# Distance_sensors.net
KiCad netlist of a schematic drawn in EAGLE
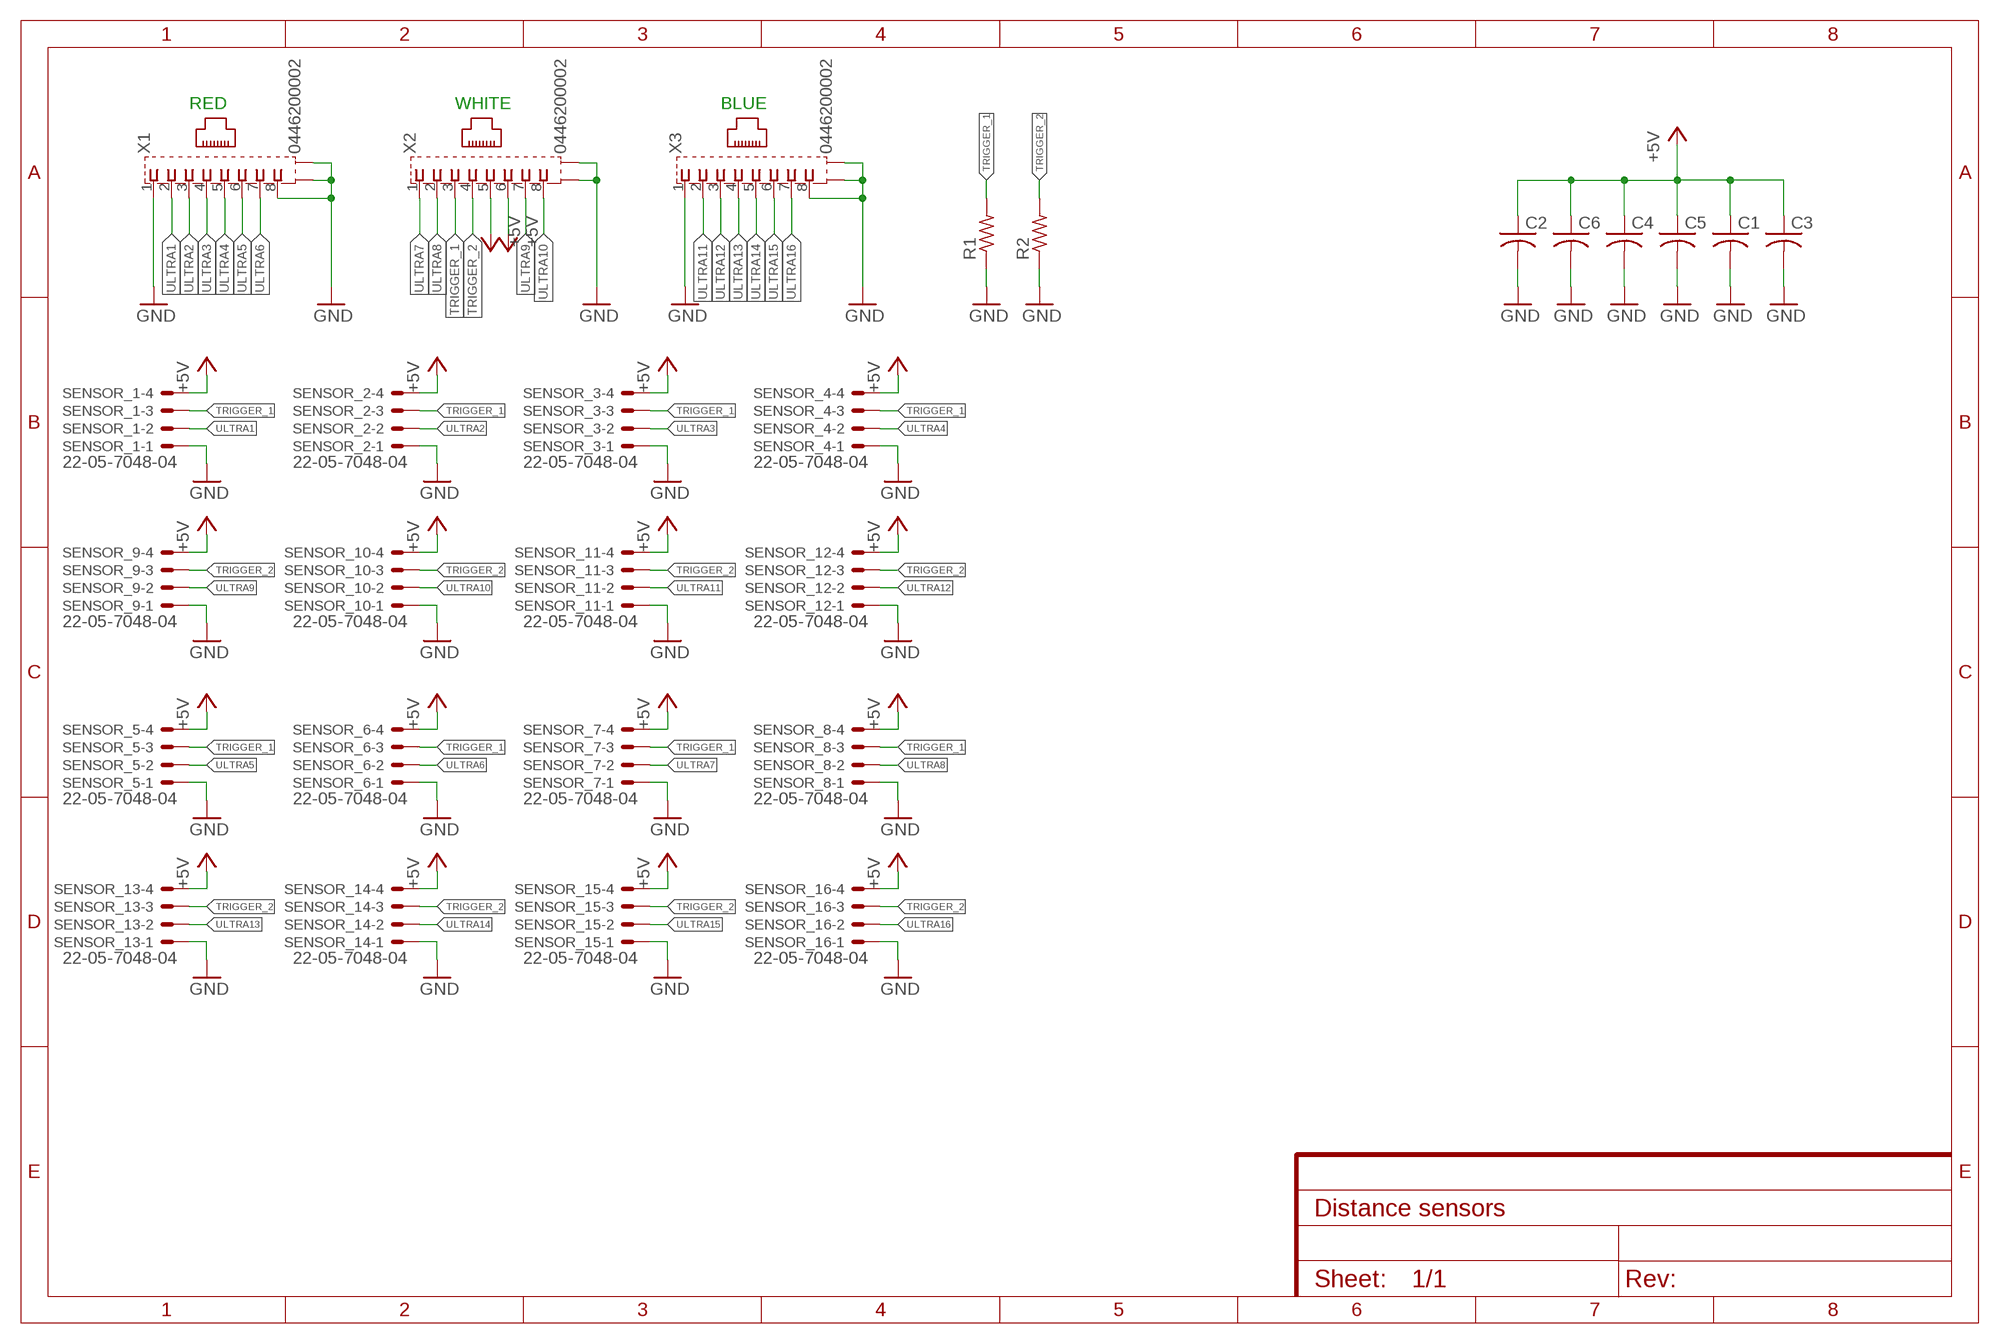
[diagram p0: schematic, sheet 1]

(export (version "E")
  (design (tool "Eeschema 10.0.6"))
  (components
    (comp (ref "C1")
      (value "C-USC0805")
      (footprint "eagle-import:C0805")
      (libsource (lib "eagle-import") (part "C-USC0805"))
    )
    (comp (ref "C2")
      (value "C-USC0805")
      (footprint "eagle-import:C0805")
      (libsource (lib "eagle-import") (part "C-USC0805"))
    )
    (comp (ref "C3")
      (value "C-USC1206")
      (footprint "eagle-import:C1206")
      (libsource (lib "eagle-import") (part "C-USC1206"))
    )
    (comp (ref "C4")
      (value "C-USC0805")
      (footprint "eagle-import:C0805")
      (libsource (lib "eagle-import") (part "C-USC0805"))
    )
    (comp (ref "C5")
      (value "C-USC0805")
      (footprint "eagle-import:C0805")
      (libsource (lib "eagle-import") (part "C-USC0805"))
    )
    (comp (ref "C6")
      (value "C-USC1206")
      (footprint "eagle-import:C1206")
      (libsource (lib "eagle-import") (part "C-USC1206"))
    )
    (comp (ref "R1")
      (value "R-US_R1206")
      (footprint "eagle-import:R1206")
      (libsource (lib "eagle-import") (part "R-US_R1206"))
    )
    (comp (ref "R2")
      (value "R-US_R1206")
      (footprint "eagle-import:R1206")
      (libsource (lib "eagle-import") (part "R-US_R1206"))
    )
    (comp (ref "SENSOR_1")
      (value "22-05-7048-04")
      (footprint "eagle-import:7395-04")
      (fields (field (name "MF") "MOLEX"))
      (libsource (lib "eagle-import") (part "22-?-0405-7048"))
    )
    (comp (ref "SENSOR_2")
      (value "22-05-7048-04")
      (footprint "eagle-import:7395-04")
      (fields (field (name "MF") "MOLEX"))
      (libsource (lib "eagle-import") (part "22-?-0405-7048"))
    )
    (comp (ref "SENSOR_3")
      (value "22-05-7048-04")
      (footprint "eagle-import:7395-04")
      (fields (field (name "MF") "MOLEX"))
      (libsource (lib "eagle-import") (part "22-?-0405-7048"))
    )
    (comp (ref "SENSOR_4")
      (value "22-05-7048-04")
      (footprint "eagle-import:7395-04")
      (fields (field (name "MF") "MOLEX"))
      (libsource (lib "eagle-import") (part "22-?-0405-7048"))
    )
    (comp (ref "SENSOR_5")
      (value "22-05-7048-04")
      (footprint "eagle-import:7395-04")
      (fields (field (name "MF") "MOLEX"))
      (libsource (lib "eagle-import") (part "22-?-0405-7048"))
    )
    (comp (ref "SENSOR_6")
      (value "22-05-7048-04")
      (footprint "eagle-import:7395-04")
      (fields (field (name "MF") "MOLEX"))
      (libsource (lib "eagle-import") (part "22-?-0405-7048"))
    )
    (comp (ref "SENSOR_7")
      (value "22-05-7048-04")
      (footprint "eagle-import:7395-04")
      (fields (field (name "MF") "MOLEX"))
      (libsource (lib "eagle-import") (part "22-?-0405-7048"))
    )
    (comp (ref "SENSOR_8")
      (value "22-05-7048-04")
      (footprint "eagle-import:7395-04")
      (fields (field (name "MF") "MOLEX"))
      (libsource (lib "eagle-import") (part "22-?-0405-7048"))
    )
    (comp (ref "SENSOR_9")
      (value "22-05-7048-04")
      (footprint "eagle-import:7395-04")
      (fields (field (name "MF") "MOLEX"))
      (libsource (lib "eagle-import") (part "22-?-0405-7048"))
    )
    (comp (ref "SENSOR_10")
      (value "22-05-7048-04")
      (footprint "eagle-import:7395-04")
      (fields (field (name "MF") "MOLEX"))
      (libsource (lib "eagle-import") (part "22-?-0405-7048"))
    )
    (comp (ref "SENSOR_11")
      (value "22-05-7048-04")
      (footprint "eagle-import:7395-04")
      (fields (field (name "MF") "MOLEX"))
      (libsource (lib "eagle-import") (part "22-?-0405-7048"))
    )
    (comp (ref "SENSOR_12")
      (value "22-05-7048-04")
      (footprint "eagle-import:7395-04")
      (fields (field (name "MF") "MOLEX"))
      (libsource (lib "eagle-import") (part "22-?-0405-7048"))
    )
    (comp (ref "SENSOR_13")
      (value "22-05-7048-04")
      (footprint "eagle-import:7395-04")
      (fields (field (name "MF") "MOLEX"))
      (libsource (lib "eagle-import") (part "22-?-0405-7048"))
    )
    (comp (ref "SENSOR_14")
      (value "22-05-7048-04")
      (footprint "eagle-import:7395-04")
      (fields (field (name "MF") "MOLEX"))
      (libsource (lib "eagle-import") (part "22-?-0405-7048"))
    )
    (comp (ref "SENSOR_15")
      (value "22-05-7048-04")
      (footprint "eagle-import:7395-04")
      (fields (field (name "MF") "MOLEX"))
      (libsource (lib "eagle-import") (part "22-?-0405-7048"))
    )
    (comp (ref "SENSOR_16")
      (value "22-05-7048-04")
      (footprint "eagle-import:7395-04")
      (fields (field (name "MF") "MOLEX"))
      (libsource (lib "eagle-import") (part "22-?-0405-7048"))
    )
    (comp (ref "X1")
      (value "0446200002")
      (footprint "eagle-import:0446200002")
      (fields (field (name "MF") "MOLEX"))
      (libsource (lib "eagle-import") (part "0446200002"))
    )
    (comp (ref "X2")
      (value "0446200002")
      (footprint "eagle-import:0446200002")
      (fields (field (name "MF") "MOLEX"))
      (libsource (lib "eagle-import") (part "0446200002"))
    )
    (comp (ref "X3")
      (value "0446200002")
      (footprint "eagle-import:0446200002")
      (fields (field (name "MF") "MOLEX"))
      (libsource (lib "eagle-import") (part "0446200002"))
    )
  )
  (nets
    (net (code "1") (name "+5V") (class "Default")
      (node (ref "C1") (pin "1") (pinfunction "1_1") (pintype "passive"))
      (node (ref "C2") (pin "1") (pinfunction "1_1") (pintype "passive"))
      (node (ref "C3") (pin "1") (pinfunction "1_1") (pintype "passive"))
      (node (ref "C4") (pin "1") (pinfunction "1_1") (pintype "passive"))
      (node (ref "C5") (pin "1") (pinfunction "1_1") (pintype "passive"))
      (node (ref "C6") (pin "1") (pinfunction "1_1") (pintype "passive"))
      (node (ref "SENSOR_1") (pin "4") (pinfunction "S_4") (pintype "passive"))
      (node (ref "SENSOR_10") (pin "4") (pinfunction "S_4") (pintype "passive"))
      (node (ref "SENSOR_11") (pin "4") (pinfunction "S_4") (pintype "passive"))
      (node (ref "SENSOR_12") (pin "4") (pinfunction "S_4") (pintype "passive"))
      (node (ref "SENSOR_13") (pin "4") (pinfunction "S_4") (pintype "passive"))
      (node (ref "SENSOR_14") (pin "4") (pinfunction "S_4") (pintype "passive"))
      (node (ref "SENSOR_15") (pin "4") (pinfunction "S_4") (pintype "passive"))
      (node (ref "SENSOR_16") (pin "4") (pinfunction "S_4") (pintype "passive"))
      (node (ref "SENSOR_2") (pin "4") (pinfunction "S_4") (pintype "passive"))
      (node (ref "SENSOR_3") (pin "4") (pinfunction "S_4") (pintype "passive"))
      (node (ref "SENSOR_4") (pin "4") (pinfunction "S_4") (pintype "passive"))
      (node (ref "SENSOR_5") (pin "4") (pinfunction "S_4") (pintype "passive"))
      (node (ref "SENSOR_6") (pin "4") (pinfunction "S_4") (pintype "passive"))
      (node (ref "SENSOR_7") (pin "4") (pinfunction "S_4") (pintype "passive"))
      (node (ref "SENSOR_8") (pin "4") (pinfunction "S_4") (pintype "passive"))
      (node (ref "SENSOR_9") (pin "4") (pinfunction "S_4") (pintype "passive"))
      (node (ref "X2") (pin "5") (pinfunction "5_5") (pintype "passive"))
      (node (ref "X2") (pin "6") (pinfunction "6_6") (pintype "passive"))
    )
    (net (code "2") (name "GND") (class "Default")
      (node (ref "C1") (pin "2") (pinfunction "2_2") (pintype "passive"))
      (node (ref "C2") (pin "2") (pinfunction "2_2") (pintype "passive"))
      (node (ref "C3") (pin "2") (pinfunction "2_2") (pintype "passive"))
      (node (ref "C4") (pin "2") (pinfunction "2_2") (pintype "passive"))
      (node (ref "C5") (pin "2") (pinfunction "2_2") (pintype "passive"))
      (node (ref "C6") (pin "2") (pinfunction "2_2") (pintype "passive"))
      (node (ref "R1") (pin "1") (pinfunction "1_1") (pintype "passive"))
      (node (ref "R2") (pin "1") (pinfunction "1_1") (pintype "passive"))
      (node (ref "SENSOR_1") (pin "1") (pinfunction "S_1") (pintype "passive"))
      (node (ref "SENSOR_10") (pin "1") (pinfunction "S_1") (pintype "passive"))
      (node (ref "SENSOR_11") (pin "1") (pinfunction "S_1") (pintype "passive"))
      (node (ref "SENSOR_12") (pin "1") (pinfunction "S_1") (pintype "passive"))
      (node (ref "SENSOR_13") (pin "1") (pinfunction "S_1") (pintype "passive"))
      (node (ref "SENSOR_14") (pin "1") (pinfunction "S_1") (pintype "passive"))
      (node (ref "SENSOR_15") (pin "1") (pinfunction "S_1") (pintype "passive"))
      (node (ref "SENSOR_16") (pin "1") (pinfunction "S_1") (pintype "passive"))
      (node (ref "SENSOR_2") (pin "1") (pinfunction "S_1") (pintype "passive"))
      (node (ref "SENSOR_3") (pin "1") (pinfunction "S_1") (pintype "passive"))
      (node (ref "SENSOR_4") (pin "1") (pinfunction "S_1") (pintype "passive"))
      (node (ref "SENSOR_5") (pin "1") (pinfunction "S_1") (pintype "passive"))
      (node (ref "SENSOR_6") (pin "1") (pinfunction "S_1") (pintype "passive"))
      (node (ref "SENSOR_7") (pin "1") (pinfunction "S_1") (pintype "passive"))
      (node (ref "SENSOR_8") (pin "1") (pinfunction "S_1") (pintype "passive"))
      (node (ref "SENSOR_9") (pin "1") (pinfunction "S_1") (pintype "passive"))
      (node (ref "X1") (pin "1") (pinfunction "1_1") (pintype "passive"))
      (node (ref "X1") (pin "8") (pinfunction "8_8") (pintype "passive"))
      (node (ref "X1") (pin "S@1") (pinfunction "S1_S@1") (pintype "passive"))
      (node (ref "X1") (pin "S@2") (pinfunction "S2_S@2") (pintype "passive"))
      (node (ref "X2") (pin "S@1") (pinfunction "S1_S@1") (pintype "passive"))
      (node (ref "X2") (pin "S@2") (pinfunction "S2_S@2") (pintype "passive"))
      (node (ref "X3") (pin "1") (pinfunction "1_1") (pintype "passive"))
      (node (ref "X3") (pin "8") (pinfunction "8_8") (pintype "passive"))
      (node (ref "X3") (pin "S@1") (pinfunction "S1_S@1") (pintype "passive"))
      (node (ref "X3") (pin "S@2") (pinfunction "S2_S@2") (pintype "passive"))
    )
    (net (code "3") (name "TRIGGER_1") (class "Default")
      (node (ref "R1") (pin "2") (pinfunction "2_2") (pintype "passive"))
      (node (ref "SENSOR_1") (pin "3") (pinfunction "S_3") (pintype "passive"))
      (node (ref "SENSOR_2") (pin "3") (pinfunction "S_3") (pintype "passive"))
      (node (ref "SENSOR_3") (pin "3") (pinfunction "S_3") (pintype "passive"))
      (node (ref "SENSOR_4") (pin "3") (pinfunction "S_3") (pintype "passive"))
      (node (ref "SENSOR_5") (pin "3") (pinfunction "S_3") (pintype "passive"))
      (node (ref "SENSOR_6") (pin "3") (pinfunction "S_3") (pintype "passive"))
      (node (ref "SENSOR_7") (pin "3") (pinfunction "S_3") (pintype "passive"))
      (node (ref "SENSOR_8") (pin "3") (pinfunction "S_3") (pintype "passive"))
      (node (ref "X2") (pin "3") (pinfunction "3_3") (pintype "passive"))
    )
    (net (code "4") (name "TRIGGER_2") (class "Default")
      (node (ref "R2") (pin "2") (pinfunction "2_2") (pintype "passive"))
      (node (ref "SENSOR_10") (pin "3") (pinfunction "S_3") (pintype "passive"))
      (node (ref "SENSOR_11") (pin "3") (pinfunction "S_3") (pintype "passive"))
      (node (ref "SENSOR_12") (pin "3") (pinfunction "S_3") (pintype "passive"))
      (node (ref "SENSOR_13") (pin "3") (pinfunction "S_3") (pintype "passive"))
      (node (ref "SENSOR_14") (pin "3") (pinfunction "S_3") (pintype "passive"))
      (node (ref "SENSOR_15") (pin "3") (pinfunction "S_3") (pintype "passive"))
      (node (ref "SENSOR_16") (pin "3") (pinfunction "S_3") (pintype "passive"))
      (node (ref "SENSOR_9") (pin "3") (pinfunction "S_3") (pintype "passive"))
      (node (ref "X2") (pin "4") (pinfunction "4_4") (pintype "passive"))
    )
    (net (code "5") (name "ULTRA1") (class "Default")
      (node (ref "SENSOR_1") (pin "2") (pinfunction "S_2") (pintype "passive"))
      (node (ref "X1") (pin "2") (pinfunction "2_2") (pintype "passive"))
    )
    (net (code "6") (name "ULTRA2") (class "Default")
      (node (ref "SENSOR_2") (pin "2") (pinfunction "S_2") (pintype "passive"))
      (node (ref "X1") (pin "3") (pinfunction "3_3") (pintype "passive"))
    )
    (net (code "7") (name "ULTRA3") (class "Default")
      (node (ref "SENSOR_3") (pin "2") (pinfunction "S_2") (pintype "passive"))
      (node (ref "X1") (pin "4") (pinfunction "4_4") (pintype "passive"))
    )
    (net (code "8") (name "ULTRA4") (class "Default")
      (node (ref "SENSOR_4") (pin "2") (pinfunction "S_2") (pintype "passive"))
      (node (ref "X1") (pin "5") (pinfunction "5_5") (pintype "passive"))
    )
    (net (code "9") (name "ULTRA5") (class "Default")
      (node (ref "SENSOR_5") (pin "2") (pinfunction "S_2") (pintype "passive"))
      (node (ref "X1") (pin "6") (pinfunction "6_6") (pintype "passive"))
    )
    (net (code "10") (name "ULTRA6") (class "Default")
      (node (ref "SENSOR_6") (pin "2") (pinfunction "S_2") (pintype "passive"))
      (node (ref "X1") (pin "7") (pinfunction "7_7") (pintype "passive"))
    )
    (net (code "11") (name "ULTRA7") (class "Default")
      (node (ref "SENSOR_7") (pin "2") (pinfunction "S_2") (pintype "passive"))
      (node (ref "X2") (pin "1") (pinfunction "1_1") (pintype "passive"))
    )
    (net (code "12") (name "ULTRA8") (class "Default")
      (node (ref "SENSOR_8") (pin "2") (pinfunction "S_2") (pintype "passive"))
      (node (ref "X2") (pin "2") (pinfunction "2_2") (pintype "passive"))
    )
    (net (code "13") (name "ULTRA9") (class "Default")
      (node (ref "SENSOR_9") (pin "2") (pinfunction "S_2") (pintype "passive"))
      (node (ref "X2") (pin "7") (pinfunction "7_7") (pintype "passive"))
    )
    (net (code "14") (name "ULTRA10") (class "Default")
      (node (ref "SENSOR_10") (pin "2") (pinfunction "S_2") (pintype "passive"))
      (node (ref "X2") (pin "8") (pinfunction "8_8") (pintype "passive"))
    )
    (net (code "15") (name "ULTRA11") (class "Default")
      (node (ref "SENSOR_11") (pin "2") (pinfunction "S_2") (pintype "passive"))
      (node (ref "X3") (pin "2") (pinfunction "2_2") (pintype "passive"))
    )
    (net (code "16") (name "ULTRA12") (class "Default")
      (node (ref "SENSOR_12") (pin "2") (pinfunction "S_2") (pintype "passive"))
      (node (ref "X3") (pin "3") (pinfunction "3_3") (pintype "passive"))
    )
    (net (code "17") (name "ULTRA13") (class "Default")
      (node (ref "SENSOR_13") (pin "2") (pinfunction "S_2") (pintype "passive"))
      (node (ref "X3") (pin "4") (pinfunction "4_4") (pintype "passive"))
    )
    (net (code "18") (name "ULTRA14") (class "Default")
      (node (ref "SENSOR_14") (pin "2") (pinfunction "S_2") (pintype "passive"))
      (node (ref "X3") (pin "5") (pinfunction "5_5") (pintype "passive"))
    )
    (net (code "19") (name "ULTRA15") (class "Default")
      (node (ref "SENSOR_15") (pin "2") (pinfunction "S_2") (pintype "passive"))
      (node (ref "X3") (pin "6") (pinfunction "6_6") (pintype "passive"))
    )
    (net (code "20") (name "ULTRA16") (class "Default")
      (node (ref "SENSOR_16") (pin "2") (pinfunction "S_2") (pintype "passive"))
      (node (ref "X3") (pin "7") (pinfunction "7_7") (pintype "passive"))
    )
  )
)
